# 3V3_AUX.net
KiCad netlist of a schematic drawn in Altium Designer
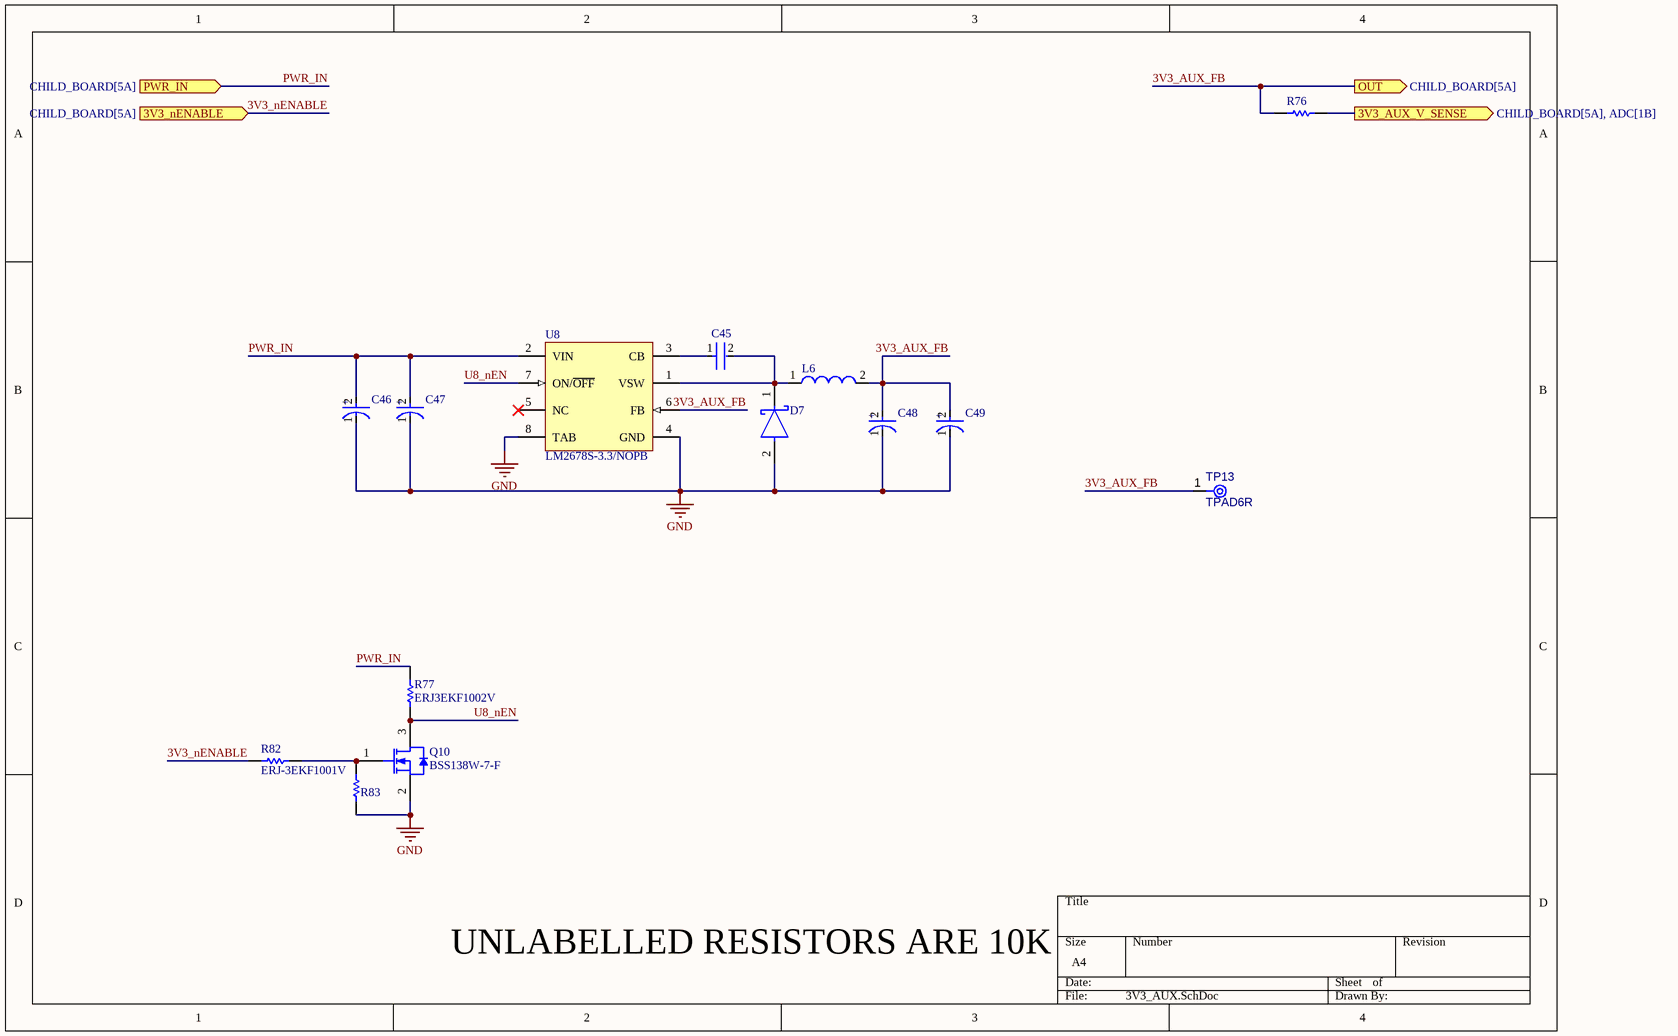
[diagram p0: 3V3_AUX.SchDoc]

(export (version "E")
  (design (tool "Eeschema 10.0.6"))
  (components
    (comp (ref "C45")
      (value "C0805C103J5RACTU")
      (footprint "FP-C0805C-DN-MFG")
      (description "CAP CER 10000PF 50V X7R 0805")
      (fields
        (field (name "MANUFACTURER") "KEMET")
        (field (name "OCTOPART") "https://octopart.com/c0805c103j5ractu-kemet-133473")
      )
      (libsource (lib "Altium Content Vault") (part "b4654b650e69147ec39a6b967a45e02"))
    )
    (comp (ref "C46")
      (value "EEHZA1V680XP")
      (footprint "FP-EEH-D8-MFG")
      (description "Conductive Polymer Hybrid Aluminum Electrolytic Capacitors 68uF ±20% 35V RADIAL SMT 6.3x7.7mm")
      (fields (field (name "VOLTAGE") "35V") (field (name "TOLERANCE") "20%"))
      (libsource (lib "Altium Content Vault") (part "a00bbbee19879c290e62620ae7e47b1"))
    )
    (comp (ref "C47")
      (value "EEHZA1V680XP")
      (footprint "FP-EEH-D8-MFG")
      (description "Conductive Polymer Hybrid Aluminum Electrolytic Capacitors 68uF ±20% 35V RADIAL SMT 6.3x7.7mm")
      (fields (field (name "VOLTAGE") "35V") (field (name "TOLERANCE") "20%"))
      (libsource (lib "Altium Content Vault") (part "a00bbbee19879c290e62620ae7e47b1"))
    )
    (comp (ref "C48")
      (value "16SVPC120M")
      (footprint "FP-OS-CON-SMT-E7-MFG")
      (description "Conductive Polymer Aluminum Solid Capacitors (OS-CON) 120uF ±20% 16V RADIAL SMT 8x6.9mm")
      (fields (field (name "VOLTAGE") "16V") (field (name "TOLERANCE") "20%"))
      (libsource (lib "Altium Content Vault") (part "cf48714ba7e38822c1575c7ec0b6d1f"))
    )
    (comp (ref "C49")
      (value "16SVPC120M")
      (footprint "FP-OS-CON-SMT-E7-MFG")
      (description "Conductive Polymer Aluminum Solid Capacitors (OS-CON) 120uF ±20% 16V RADIAL SMT 8x6.9mm")
      (fields (field (name "VOLTAGE") "16V") (field (name "TOLERANCE") "20%"))
      (libsource (lib "Altium Content Vault") (part "cf48714ba7e38822c1575c7ec0b6d1f"))
    )
    (comp (ref "D7")
      (value "B540C-13-F")
      (footprint "FP-SMC-MFG")
      (description "DIODE SCHOTTKY 40V 5A SMC")
      (fields
        (field (name "OCTOPART") "https://octopart.com/b540c-13-f-diodes+inc.-325873")
        (field (name "MANUFACTURER") "Diodes Inc.")
      )
      (libsource (lib "Altium Content Vault") (part "1d6ec82d83fb6aee721767c19dac4b9"))
    )
    (comp (ref "L6")
      (value "74477110")
      (footprint "WE-PD-L")
      (description "SMD-Shielded Power Inductor WE-PD, L = 10.0 µH")
      (libsource (lib "Altium Content Vault") (part "PAS-IND-INDUCTOR-2"))
    )
    (comp (ref "Q10")
      (value "BSS138W-7-F")
      (footprint "DIOD-SOT323-3_V")
      (fields (field (name "MANUFACTURER") "DiodesIncorporated"))
      (libsource (lib "Altium Content Vault") (part "NEMOS-GSD-3"))
    )
    (comp (ref "R76")
      (value "ERJ3EKF1002V")
      (footprint "RESC1609X55X30LL15T15")
      (description "Chip Resistor, 10 KOhm, +/- 1%, 0.1 W, -55 to 155 degC, 0603 (1608 Metric), RoHS, Tape and Reel")
      (fields (field (name "TOLERANCE") "1%") (field (name "MANUFACTURER") "Panasonic"))
      (libsource (lib "Altium Content Vault") (part "RES-2"))
    )
    (comp (ref "R77")
      (value "ERJ3EKF1002V")
      (footprint "RESC1609X55X30LL15T15")
      (description "Chip Resistor, 10 KOhm, +/- 1%, 0.1 W, -55 to 155 degC, 0603 (1608 Metric), RoHS, Tape and Reel")
      (fields (field (name "TOLERANCE") "1%") (field (name "MANUFACTURER") "Panasonic"))
      (libsource (lib "Altium Content Vault") (part "RES-2"))
    )
    (comp (ref "R82")
      (value "ERJ-3EKF1001V")
      (footprint "RESC1608X55X30LL15T15")
      (fields (field (name "MANUFACTURER") "Panasonic"))
      (libsource (lib "Altium Content Vault") (part "RES"))
    )
    (comp (ref "R83")
      (value "ERJ3EKF1002V")
      (footprint "RESC1609X55X30LL15T15")
      (description "Chip Resistor, 10 KOhm, +/- 1%, 0.1 W, -55 to 155 degC, 0603 (1608 Metric), RoHS, Tape and Reel")
      (fields (field (name "TOLERANCE") "1%") (field (name "MANUFACTURER") "Panasonic"))
      (libsource (lib "Altium Content Vault") (part "RES-2"))
    )
    (comp (ref "TP13")
      (value "TPAD6R")
      (footprint "TP06R")
      (description "0.6mm round")
      (libsource (lib "uORocketry Hardware") (part "CMP-001-0001-4"))
    )
    (comp (ref "U8")
      (value "LM2678S-3.3/NOPB")
      (footprint "KTW0007B_N")
      (description "SIMPLE SWITCHER® High Efficiency 5A Step-Down Voltage Regulator, 7-pin TO-263, Pb-Free")
      (fields (field (name "MANUFACTURER") "Texas Instruments"))
      (libsource (lib "Altium Content Vault") (part "PM-REG-LM2678S"))
    )
  )
  (nets
    (net (code "1") (name "/3V3_AUX_FB") (class "Default")
      (node (ref "C48") (pin "2") (pinfunction "A_2") (pintype "passive"))
      (node (ref "C49") (pin "2") (pinfunction "A_2") (pintype "passive"))
      (node (ref "L6") (pin "2") (pinfunction "2_2") (pintype "passive"))
      (node (ref "R76") (pin "1") (pinfunction "1_1") (pintype "passive"))
      (node (ref "TP13") (pin "1") (pinfunction "TP_1") (pintype "passive"))
      (node (ref "U8") (pin "6") (pinfunction "FB_6") (pintype "input"))
    )
    (net (code "2") (name "/3V3_AUX_V_SENSE") (class "Default")
      (node (ref "R76") (pin "2") (pinfunction "2_2") (pintype "passive"))
    )
    (net (code "3") (name "/3V3_nENABLE") (class "Default")
      (node (ref "R82") (pin "1") (pinfunction "1_1") (pintype "passive"))
    )
    (net (code "4") (name "/PWR_IN") (class "Default")
      (node (ref "C46") (pin "2") (pinfunction "A_2") (pintype "passive"))
      (node (ref "C47") (pin "2") (pinfunction "A_2") (pintype "passive"))
      (node (ref "R77") (pin "2") (pinfunction "2_2") (pintype "passive"))
      (node (ref "U8") (pin "2") (pinfunction "VIN_2") (pintype "power_in"))
    )
    (net (code "5") (name "/U8_nEN") (class "Default")
      (node (ref "Q10") (pin "3") (pinfunction "D_3") (pintype "passive"))
      (node (ref "R77") (pin "1") (pinfunction "1_1") (pintype "passive"))
      (node (ref "U8") (pin "7") (pinfunction "ON/~{OFF}_7") (pintype "input"))
    )
    (net (code "6") (name "GND") (class "Default")
      (node (ref "C46") (pin "1") (pinfunction "C_1") (pintype "passive"))
      (node (ref "C47") (pin "1") (pinfunction "C_1") (pintype "passive"))
      (node (ref "C48") (pin "1") (pinfunction "C_1") (pintype "passive"))
      (node (ref "C49") (pin "1") (pinfunction "C_1") (pintype "passive"))
      (node (ref "D7") (pin "2") (pinfunction "A_2") (pintype "passive"))
      (node (ref "Q10") (pin "2") (pinfunction "S_2") (pintype "passive"))
      (node (ref "R83") (pin "1") (pinfunction "1_1") (pintype "passive"))
      (node (ref "U8") (pin "4") (pinfunction "GND_4") (pintype "power_in"))
      (node (ref "U8") (pin "8") (pinfunction "TAB_8") (pintype "power_in"))
    )
    (net (code "7") (name "Net-(D7-C)") (class "Default")
      (node (ref "C45") (pin "2") (pinfunction "2_2") (pintype "passive"))
      (node (ref "D7") (pin "1") (pinfunction "C_1") (pintype "passive"))
      (node (ref "L6") (pin "1") (pinfunction "1_1") (pintype "passive"))
      (node (ref "U8") (pin "1") (pinfunction "VSW_1") (pintype "power_in"))
    )
    (net (code "8") (name "Net-(Q10-G)") (class "Default")
      (node (ref "Q10") (pin "1") (pinfunction "G_1") (pintype "passive"))
      (node (ref "R82") (pin "2") (pinfunction "2_2") (pintype "passive"))
      (node (ref "R83") (pin "2") (pinfunction "2_2") (pintype "passive"))
    )
    (net (code "9") (name "Net-(U8-CB)") (class "Default")
      (node (ref "C45") (pin "1") (pinfunction "1_1") (pintype "passive"))
      (node (ref "U8") (pin "3") (pinfunction "CB_3") (pintype "passive"))
    )
    (net (code "10") (name "unconnected-(U8-NC-Pad5)") (class "Default")
      (node (ref "U8") (pin "5") (pinfunction "NC_5") (pintype "passive+no_connect"))
    )
  )
)
